# Power_MPU.net
KiCad netlist of a schematic drawn in Altium Designer
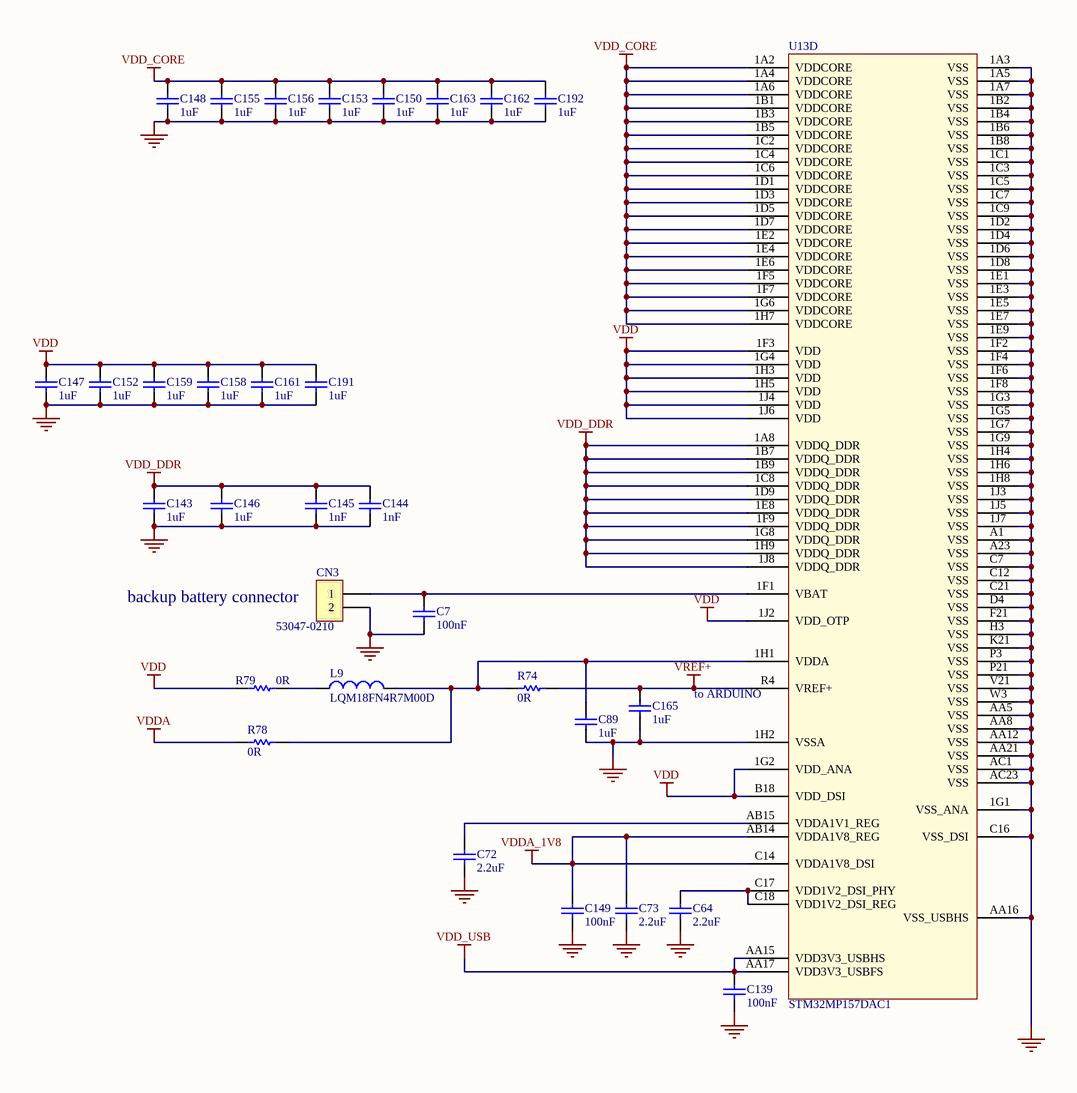
[diagram p0: Power_MPU.SchDoc]

(export (version "E")
  (design (tool "Eeschema 10.0.6"))
  (components
    (comp (ref "C7")
      (value "100nF")
      (footprint "C0402")
      (description "Capacitor,100nF,16V,X7R,10%,0402")
      (fields
        (field (name "INTERNAL_PART_NUMBER") "MCD-00006")
        (field (name "MANUFACTURER_PART_NUMBER") "CC0402KRX7R7BB104")
        (field (name "PROVIDED_BY") "SUBCO")
      )
      (libsource (lib "MCD_PARTS_database") (part "Capacitor"))
    )
    (comp (ref "C64")
      (value "2.2uF")
      (footprint "C0402")
      (description "Capacitor,MLCC,2.2uF,6V3,X5R,10%,0402,T=0.5")
      (fields
        (field (name "INTERNAL_PART_NUMBER") "MCD-01823")
        (field (name "MANUFACTURER_PART_NUMBER") "GRM155R60J225KE95D")
        (field (name "PROVIDED_BY") "SUBCO")
      )
      (libsource (lib "MCD_PARTS_database") (part "Capacitor"))
    )
    (comp (ref "C72")
      (value "2.2uF")
      (footprint "C0402")
      (description "Capacitor,MLCC,2.2uF,6V3,X5R,10%,0402,T=0.5")
      (fields
        (field (name "INTERNAL_PART_NUMBER") "MCD-01823")
        (field (name "MANUFACTURER_PART_NUMBER") "GRM155R60J225KE95D")
        (field (name "PROVIDED_BY") "SUBCO")
      )
      (libsource (lib "MCD_PARTS_database") (part "Capacitor"))
    )
    (comp (ref "C73")
      (value "2.2uF")
      (footprint "C0402")
      (description "Capacitor,MLCC,2.2uF,6V3,X5R,10%,0402,T=0.5")
      (fields
        (field (name "INTERNAL_PART_NUMBER") "MCD-01823")
        (field (name "MANUFACTURER_PART_NUMBER") "GRM155R60J225KE95D")
        (field (name "PROVIDED_BY") "SUBCO")
      )
      (libsource (lib "MCD_PARTS_database") (part "Capacitor"))
    )
    (comp (ref "C89")
      (value "1uF")
      (footprint "C0402")
      (description "Capacitor,1uF,6V3,X5R,10%,0402")
      (fields
        (field (name "INTERNAL_PART_NUMBER") "MCD-00095")
        (field (name "MANUFACTURER_PART_NUMBER") "GRM155R61E105KA12")
        (field (name "PROVIDED_BY") "SUBCO")
      )
      (libsource (lib "MCD_PARTS_database") (part "Capacitor"))
    )
    (comp (ref "C139")
      (value "100nF")
      (footprint "C0402")
      (description "Capacitor,100nF,16V,X7R,10%,0402")
      (fields
        (field (name "INTERNAL_PART_NUMBER") "MCD-00006")
        (field (name "MANUFACTURER_PART_NUMBER") "CC0402KRX7R7BB104")
        (field (name "PROVIDED_BY") "SUBCO")
      )
      (libsource (lib "MCD_PARTS_database") (part "Capacitor"))
    )
    (comp (ref "C143")
      (value "1uF")
      (footprint "C0402")
      (description "Capacitor,1uF,6V3,X5R,10%,0402")
      (fields
        (field (name "INTERNAL_PART_NUMBER") "MCD-00095")
        (field (name "MANUFACTURER_PART_NUMBER") "GRM155R61E105KA12")
        (field (name "PROVIDED_BY") "SUBCO")
      )
      (libsource (lib "MCD_PARTS_database") (part "Capacitor"))
    )
    (comp (ref "C144")
      (value "1nF")
      (footprint "C0402")
      (description "Capacitor,1nF,16V,X7R,10%,0402")
      (fields
        (field (name "INTERNAL_PART_NUMBER") "MCD-00198")
        (field (name "MANUFACTURER_PART_NUMBER") "CC0402KRX7R7BB102")
        (field (name "PROVIDED_BY") "SUBCO")
      )
      (libsource (lib "MCD_PARTS_database") (part "Capacitor"))
    )
    (comp (ref "C145")
      (value "1nF")
      (footprint "C0402")
      (description "Capacitor,1nF,16V,X7R,10%,0402")
      (fields
        (field (name "INTERNAL_PART_NUMBER") "MCD-00198")
        (field (name "MANUFACTURER_PART_NUMBER") "CC0402KRX7R7BB102")
        (field (name "PROVIDED_BY") "SUBCO")
      )
      (libsource (lib "MCD_PARTS_database") (part "Capacitor"))
    )
    (comp (ref "C146")
      (value "1uF")
      (footprint "C0402")
      (description "Capacitor,1uF,6V3,X5R,10%,0402")
      (fields
        (field (name "INTERNAL_PART_NUMBER") "MCD-00095")
        (field (name "MANUFACTURER_PART_NUMBER") "GRM155R61E105KA12")
        (field (name "PROVIDED_BY") "SUBCO")
      )
      (libsource (lib "MCD_PARTS_database") (part "Capacitor"))
    )
    (comp (ref "C147")
      (value "1uF")
      (footprint "C0402")
      (description "Capacitor,1uF,6V3,X5R,10%,0402")
      (fields
        (field (name "INTERNAL_PART_NUMBER") "MCD-00095")
        (field (name "MANUFACTURER_PART_NUMBER") "GRM155R61E105KA12")
        (field (name "PROVIDED_BY") "SUBCO")
      )
      (libsource (lib "MCD_PARTS_database") (part "Capacitor"))
    )
    (comp (ref "C148")
      (value "1uF")
      (footprint "C0402")
      (description "Capacitor,1uF,6V3,X5R,10%,0402")
      (fields
        (field (name "INTERNAL_PART_NUMBER") "MCD-00095")
        (field (name "MANUFACTURER_PART_NUMBER") "GRM155R61E105KA12")
        (field (name "PROVIDED_BY") "SUBCO")
      )
      (libsource (lib "MCD_PARTS_database") (part "Capacitor"))
    )
    (comp (ref "C149")
      (value "100nF")
      (footprint "C0402")
      (description "Capacitor,100nF,16V,X7R,10%,0402")
      (fields
        (field (name "INTERNAL_PART_NUMBER") "MCD-00006")
        (field (name "MANUFACTURER_PART_NUMBER") "CC0402KRX7R7BB104")
        (field (name "PROVIDED_BY") "SUBCO")
      )
      (libsource (lib "MCD_PARTS_database") (part "Capacitor"))
    )
    (comp (ref "C150")
      (value "1uF")
      (footprint "C0402")
      (description "Capacitor,1uF,6V3,X5R,10%,0402")
      (fields
        (field (name "INTERNAL_PART_NUMBER") "MCD-00095")
        (field (name "MANUFACTURER_PART_NUMBER") "GRM155R61E105KA12")
        (field (name "PROVIDED_BY") "SUBCO")
      )
      (libsource (lib "MCD_PARTS_database") (part "Capacitor"))
    )
    (comp (ref "C152")
      (value "1uF")
      (footprint "C0402")
      (description "Capacitor,1uF,6V3,X5R,10%,0402")
      (fields
        (field (name "INTERNAL_PART_NUMBER") "MCD-00095")
        (field (name "MANUFACTURER_PART_NUMBER") "GRM155R61E105KA12")
        (field (name "PROVIDED_BY") "SUBCO")
      )
      (libsource (lib "MCD_PARTS_database") (part "Capacitor"))
    )
    (comp (ref "C153")
      (value "1uF")
      (footprint "C0402")
      (description "Capacitor,1uF,6V3,X5R,10%,0402")
      (fields
        (field (name "INTERNAL_PART_NUMBER") "MCD-00095")
        (field (name "MANUFACTURER_PART_NUMBER") "GRM155R61E105KA12")
        (field (name "PROVIDED_BY") "SUBCO")
      )
      (libsource (lib "MCD_PARTS_database") (part "Capacitor"))
    )
    (comp (ref "C155")
      (value "1uF")
      (footprint "C0402")
      (description "Capacitor,1uF,6V3,X5R,10%,0402")
      (fields
        (field (name "INTERNAL_PART_NUMBER") "MCD-00095")
        (field (name "MANUFACTURER_PART_NUMBER") "GRM155R61E105KA12")
        (field (name "PROVIDED_BY") "SUBCO")
      )
      (libsource (lib "MCD_PARTS_database") (part "Capacitor"))
    )
    (comp (ref "C156")
      (value "1uF")
      (footprint "C0402")
      (description "Capacitor,1uF,6V3,X5R,10%,0402")
      (fields
        (field (name "INTERNAL_PART_NUMBER") "MCD-00095")
        (field (name "MANUFACTURER_PART_NUMBER") "GRM155R61E105KA12")
        (field (name "PROVIDED_BY") "SUBCO")
      )
      (libsource (lib "MCD_PARTS_database") (part "Capacitor"))
    )
    (comp (ref "C158")
      (value "1uF")
      (footprint "C0402")
      (description "Capacitor,1uF,6V3,X5R,10%,0402")
      (fields
        (field (name "INTERNAL_PART_NUMBER") "MCD-00095")
        (field (name "MANUFACTURER_PART_NUMBER") "GRM155R61E105KA12")
        (field (name "PROVIDED_BY") "SUBCO")
      )
      (libsource (lib "MCD_PARTS_database") (part "Capacitor"))
    )
    (comp (ref "C159")
      (value "1uF")
      (footprint "C0402")
      (description "Capacitor,1uF,6V3,X5R,10%,0402")
      (fields
        (field (name "INTERNAL_PART_NUMBER") "MCD-00095")
        (field (name "MANUFACTURER_PART_NUMBER") "GRM155R61E105KA12")
        (field (name "PROVIDED_BY") "SUBCO")
      )
      (libsource (lib "MCD_PARTS_database") (part "Capacitor"))
    )
    (comp (ref "C161")
      (value "1uF")
      (footprint "C0402")
      (description "Capacitor,1uF,6V3,X5R,10%,0402")
      (fields
        (field (name "INTERNAL_PART_NUMBER") "MCD-00095")
        (field (name "MANUFACTURER_PART_NUMBER") "GRM155R61E105KA12")
        (field (name "PROVIDED_BY") "SUBCO")
      )
      (libsource (lib "MCD_PARTS_database") (part "Capacitor"))
    )
    (comp (ref "C162")
      (value "1uF")
      (footprint "C0402")
      (description "Capacitor,1uF,6V3,X5R,10%,0402")
      (fields
        (field (name "INTERNAL_PART_NUMBER") "MCD-00095")
        (field (name "MANUFACTURER_PART_NUMBER") "GRM155R61E105KA12")
        (field (name "PROVIDED_BY") "SUBCO")
      )
      (libsource (lib "MCD_PARTS_database") (part "Capacitor"))
    )
    (comp (ref "C163")
      (value "1uF")
      (footprint "C0402")
      (description "Capacitor,1uF,6V3,X5R,10%,0402")
      (fields
        (field (name "INTERNAL_PART_NUMBER") "MCD-00095")
        (field (name "MANUFACTURER_PART_NUMBER") "GRM155R61E105KA12")
        (field (name "PROVIDED_BY") "SUBCO")
      )
      (libsource (lib "MCD_PARTS_database") (part "Capacitor"))
    )
    (comp (ref "C165")
      (value "1uF")
      (footprint "C0402")
      (description "Capacitor,1uF,6V3,X5R,10%,0402")
      (fields
        (field (name "INTERNAL_PART_NUMBER") "MCD-00095")
        (field (name "MANUFACTURER_PART_NUMBER") "GRM155R61E105KA12")
        (field (name "PROVIDED_BY") "SUBCO")
      )
      (libsource (lib "MCD_PARTS_database") (part "Capacitor"))
    )
    (comp (ref "C191")
      (value "1uF")
      (footprint "C0402")
      (description "Capacitor,1uF,6V3,X5R,10%,0402")
      (fields
        (field (name "INTERNAL_PART_NUMBER") "MCD-00095")
        (field (name "MANUFACTURER_PART_NUMBER") "GRM155R61E105KA12")
        (field (name "PROVIDED_BY") "SUBCO")
      )
      (libsource (lib "MCD_PARTS_database") (part "Capacitor"))
    )
    (comp (ref "C192")
      (value "1uF")
      (footprint "C0402")
      (description "Capacitor,1uF,6V3,X5R,10%,0402")
      (fields
        (field (name "INTERNAL_PART_NUMBER") "MCD-00095")
        (field (name "MANUFACTURER_PART_NUMBER") "GRM155R61E105KA12")
        (field (name "PROVIDED_BY") "SUBCO")
      )
      (libsource (lib "MCD_PARTS_database") (part "Capacitor"))
    )
    (comp (ref "CN3")
      (value "53047-0210")
      (footprint "CON_MOLEX_53047-0210")
      (description "Header 2 circuits, 1.25mm Pitch ,  Vertical, with Friction Lock")
      (fields
        (field (name "INTERNAL_PART_NUMBER") "MCD-00655")
        (field (name "MANUFACTURER") "MOLEX")
        (field (name "PROVIDED_BY") "SUBCO")
      )
      (libsource (lib "MCD_PARTS_database") (part "Header 2x1"))
    )
    (comp (ref "L9")
      (value "LQM18FN4R7M00D")
      (footprint "L0603")
      (description "IND 4.7µH 20% 80mA 600mhom 0603")
      (fields
        (field (name "INTERNAL_PART_NUMBER") "MCD-01134")
        (field (name "MANUFACTURER") "MURATA")
        (field (name "PROVIDED_BY") "SUBCO")
      )
      (libsource (lib "MCD_PARTS_database") (part "LQM18FN4R7M00D"))
    )
    (comp (ref "R74")
      (value "0R")
      (footprint "R0402")
      (description "Resistor,0R,0402,5%,1/16W")
      (fields
        (field (name "INTERNAL_PART_NUMBER") "MCD-00052")
        (field (name "MANUFACTURER_PART_NUMBER") "RC0402JR-070RL")
        (field (name "PROVIDED_BY") "SUBCO")
      )
      (libsource (lib "MCD_PARTS_database") (part "Resistor"))
    )
    (comp (ref "R78")
      (value "0R")
      (footprint "R0402")
      (description "Resistor,0R,0402,5%,1/16W")
      (fields
        (field (name "INTERNAL_PART_NUMBER") "MCD-00052")
        (field (name "MANUFACTURER_PART_NUMBER") "RC0402JR-070RL")
        (field (name "PROVIDED_BY") "SUBCO")
      )
      (libsource (lib "MCD_PARTS_database") (part "Resistor"))
    )
    (comp (ref "R79")
      (value "0R")
      (footprint "R0402")
      (description "Resistor,0R,0402,5%,1/16W")
      (fields
        (field (name "INTERNAL_PART_NUMBER") "MCD-00052")
        (field (name "MANUFACTURER_PART_NUMBER") "RC0402JR-070RL")
        (field (name "PROVIDED_BY") "SUBCO")
      )
      (libsource (lib "MCD_PARTS_database") (part "Resistor"))
    )
    (comp (ref "U13")
      (value "STM32MP157DAC1")
      (footprint "ICC_TFBGA361_12X12_STM32MP157CAC3_P050-065")
      (description "MPU TFBGA12x12 without crypto increased frequency")
      (fields
        (field (name "INTERNAL_PART_NUMBER") "MCD-02020")
        (field (name "MANUFACTURER") "STMICROELECTRONICS")
        (field (name "PROVIDED_BY") "SUBCO with ST control")
      )
      (libsource (lib "MCD_PARTS_database") (part "STM32MP157DAC1"))
    )
  )
  (nets
    (net (code "1") (name "GND") (class "Default")
      (node (ref "C139") (pin "1") (pinfunction "1_1") (pintype "passive"))
      (node (ref "C143") (pin "1") (pinfunction "1_1") (pintype "passive"))
      (node (ref "C144") (pin "1") (pinfunction "1_1") (pintype "passive"))
      (node (ref "C145") (pin "1") (pinfunction "1_1") (pintype "passive"))
      (node (ref "C146") (pin "1") (pinfunction "1_1") (pintype "passive"))
      (node (ref "C147") (pin "1") (pinfunction "1_1") (pintype "passive"))
      (node (ref "C148") (pin "1") (pinfunction "1_1") (pintype "passive"))
      (node (ref "C149") (pin "1") (pinfunction "1_1") (pintype "passive"))
      (node (ref "C150") (pin "1") (pinfunction "1_1") (pintype "passive"))
      (node (ref "C152") (pin "1") (pinfunction "1_1") (pintype "passive"))
      (node (ref "C153") (pin "1") (pinfunction "1_1") (pintype "passive"))
      (node (ref "C155") (pin "1") (pinfunction "1_1") (pintype "passive"))
      (node (ref "C156") (pin "1") (pinfunction "1_1") (pintype "passive"))
      (node (ref "C158") (pin "1") (pinfunction "1_1") (pintype "passive"))
      (node (ref "C159") (pin "1") (pinfunction "1_1") (pintype "passive"))
      (node (ref "C161") (pin "1") (pinfunction "1_1") (pintype "passive"))
      (node (ref "C162") (pin "1") (pinfunction "1_1") (pintype "passive"))
      (node (ref "C163") (pin "1") (pinfunction "1_1") (pintype "passive"))
      (node (ref "C165") (pin "1") (pinfunction "1_1") (pintype "passive"))
      (node (ref "C191") (pin "1") (pinfunction "1_1") (pintype "passive"))
      (node (ref "C192") (pin "1") (pinfunction "1_1") (pintype "passive"))
      (node (ref "C64") (pin "2") (pinfunction "2_2") (pintype "passive"))
      (node (ref "C7") (pin "1") (pinfunction "1_1") (pintype "passive"))
      (node (ref "C72") (pin "2") (pinfunction "2_2") (pintype "passive"))
      (node (ref "C73") (pin "2") (pinfunction "2_2") (pintype "passive"))
      (node (ref "C89") (pin "1") (pinfunction "1_1") (pintype "passive"))
      (node (ref "CN3") (pin "2") (pinfunction "2_2") (pintype "passive"))
      (node (ref "U13") (pin "1A3") (pinfunction "VSS_1A3") (pintype "passive"))
      (node (ref "U13") (pin "1A5") (pinfunction "VSS_1A5") (pintype "passive"))
      (node (ref "U13") (pin "1A7") (pinfunction "VSS_1A7") (pintype "passive"))
      (node (ref "U13") (pin "1B2") (pinfunction "VSS_1B2") (pintype "passive"))
      (node (ref "U13") (pin "1B4") (pinfunction "VSS_1B4") (pintype "passive"))
      (node (ref "U13") (pin "1B6") (pinfunction "VSS_1B6") (pintype "passive"))
      (node (ref "U13") (pin "1B8") (pinfunction "VSS_1B8") (pintype "passive"))
      (node (ref "U13") (pin "1C1") (pinfunction "VSS_1C1") (pintype "passive"))
      (node (ref "U13") (pin "1C3") (pinfunction "VSS_1C3") (pintype "passive"))
      (node (ref "U13") (pin "1C5") (pinfunction "VSS_1C5") (pintype "passive"))
      (node (ref "U13") (pin "1C7") (pinfunction "VSS_1C7") (pintype "passive"))
      (node (ref "U13") (pin "1C9") (pinfunction "VSS_1C9") (pintype "passive"))
      (node (ref "U13") (pin "1D2") (pinfunction "VSS_1D2") (pintype "passive"))
      (node (ref "U13") (pin "1D4") (pinfunction "VSS_1D4") (pintype "passive"))
      (node (ref "U13") (pin "1D6") (pinfunction "VSS_1D6") (pintype "passive"))
      (node (ref "U13") (pin "1D8") (pinfunction "VSS_1D8") (pintype "passive"))
      (node (ref "U13") (pin "1E1") (pinfunction "VSS_1E1") (pintype "passive"))
      (node (ref "U13") (pin "1E3") (pinfunction "VSS_1E3") (pintype "passive"))
      (node (ref "U13") (pin "1E5") (pinfunction "VSS_1E5") (pintype "passive"))
      (node (ref "U13") (pin "1E7") (pinfunction "VSS_1E7") (pintype "passive"))
      (node (ref "U13") (pin "1E9") (pinfunction "VSS_1E9") (pintype "passive"))
      (node (ref "U13") (pin "1F2") (pinfunction "VSS_1F2") (pintype "passive"))
      (node (ref "U13") (pin "1F4") (pinfunction "VSS_1F4") (pintype "passive"))
      (node (ref "U13") (pin "1F6") (pinfunction "VSS_1F6") (pintype "passive"))
      (node (ref "U13") (pin "1F8") (pinfunction "VSS_1F8") (pintype "passive"))
      (node (ref "U13") (pin "1G1") (pinfunction "VSS_ANA_1G1") (pintype "passive"))
      (node (ref "U13") (pin "1G3") (pinfunction "VSS_1G3") (pintype "passive"))
      (node (ref "U13") (pin "1G5") (pinfunction "VSS_1G5") (pintype "passive"))
      (node (ref "U13") (pin "1G7") (pinfunction "VSS_1G7") (pintype "passive"))
      (node (ref "U13") (pin "1G9") (pinfunction "VSS_1G9") (pintype "passive"))
      (node (ref "U13") (pin "1H2") (pinfunction "VSSA_1H2") (pintype "passive"))
      (node (ref "U13") (pin "1H4") (pinfunction "VSS_1H4") (pintype "passive"))
      (node (ref "U13") (pin "1H6") (pinfunction "VSS_1H6") (pintype "passive"))
      (node (ref "U13") (pin "1H8") (pinfunction "VSS_1H8") (pintype "passive"))
      (node (ref "U13") (pin "1J3") (pinfunction "VSS_1J3") (pintype "passive"))
      (node (ref "U13") (pin "1J5") (pinfunction "VSS_1J5") (pintype "passive"))
      (node (ref "U13") (pin "1J7") (pinfunction "VSS_1J7") (pintype "passive"))
      (node (ref "U13") (pin "A1") (pinfunction "VSS_A1") (pintype "passive"))
      (node (ref "U13") (pin "A23") (pinfunction "VSS_A23") (pintype "passive"))
      (node (ref "U13") (pin "AA12") (pinfunction "VSS_AA12") (pintype "passive"))
      (node (ref "U13") (pin "AA16") (pinfunction "VSS_USBHS_AA16") (pintype "passive"))
      (node (ref "U13") (pin "AA21") (pinfunction "VSS_AA21") (pintype "passive"))
      (node (ref "U13") (pin "AA5") (pinfunction "VSS_AA5") (pintype "passive"))
      (node (ref "U13") (pin "AA8") (pinfunction "VSS_AA8") (pintype "passive"))
      (node (ref "U13") (pin "AC1") (pinfunction "VSS_AC1") (pintype "passive"))
      (node (ref "U13") (pin "AC23") (pinfunction "VSS_AC23") (pintype "passive"))
      (node (ref "U13") (pin "C12") (pinfunction "VSS_C12") (pintype "passive"))
      (node (ref "U13") (pin "C16") (pinfunction "VSS_DSI_C16") (pintype "passive"))
      (node (ref "U13") (pin "C21") (pinfunction "VSS_C21") (pintype "passive"))
      (node (ref "U13") (pin "C7") (pinfunction "VSS_C7") (pintype "passive"))
      (node (ref "U13") (pin "D4") (pinfunction "VSS_D4") (pintype "passive"))
      (node (ref "U13") (pin "F21") (pinfunction "VSS_F21") (pintype "passive"))
      (node (ref "U13") (pin "H3") (pinfunction "VSS_H3") (pintype "passive"))
      (node (ref "U13") (pin "K21") (pinfunction "VSS_K21") (pintype "passive"))
      (node (ref "U13") (pin "P21") (pinfunction "VSS_P21") (pintype "passive"))
      (node (ref "U13") (pin "P3") (pinfunction "VSS_P3") (pintype "passive"))
      (node (ref "U13") (pin "V21") (pinfunction "VSS_V21") (pintype "passive"))
      (node (ref "U13") (pin "W3") (pinfunction "VSS_W3") (pintype "passive"))
    )
    (net (code "2") (name "Net-(L9-Pad1)") (class "Default")
      (node (ref "L9") (pin "1") (pinfunction "1_1") (pintype "passive"))
      (node (ref "R79") (pin "2") (pinfunction "2_2") (pintype "passive"))
    )
    (net (code "3") (name "Net-(U13D-VBAT)") (class "Default")
      (node (ref "C7") (pin "2") (pinfunction "2_2") (pintype "passive"))
      (node (ref "CN3") (pin "1") (pinfunction "1_1") (pintype "passive"))
      (node (ref "U13") (pin "1F1") (pinfunction "VBAT_1F1") (pintype "passive"))
    )
    (net (code "4") (name "Net-(U13D-VDD1V2_DSI_PHY)") (class "Default")
      (node (ref "C64") (pin "1") (pinfunction "1_1") (pintype "passive"))
      (node (ref "U13") (pin "C17") (pinfunction "VDD1V2_DSI_PHY_C17") (pintype "passive"))
      (node (ref "U13") (pin "C18") (pinfunction "VDD1V2_DSI_REG_C18") (pintype "passive"))
    )
    (net (code "5") (name "Net-(U13D-VDDA)") (class "Default")
      (node (ref "C89") (pin "2") (pinfunction "2_2") (pintype "passive"))
      (node (ref "L9") (pin "2") (pinfunction "2_2") (pintype "passive"))
      (node (ref "R74") (pin "1") (pinfunction "1_1") (pintype "passive"))
      (node (ref "R78") (pin "2") (pinfunction "2_2") (pintype "passive"))
      (node (ref "U13") (pin "1H1") (pinfunction "VDDA_1H1") (pintype "passive"))
    )
    (net (code "6") (name "Net-(U13D-VDDA1V1_REG)") (class "Default")
      (node (ref "C72") (pin "1") (pinfunction "1_1") (pintype "passive"))
      (node (ref "U13") (pin "AB15") (pinfunction "VDDA1V1_REG_AB15") (pintype "passive"))
    )
    (net (code "7") (name "VDD") (class "Default")
      (node (ref "C147") (pin "2") (pinfunction "2_2") (pintype "passive"))
      (node (ref "C152") (pin "2") (pinfunction "2_2") (pintype "passive"))
      (node (ref "C158") (pin "2") (pinfunction "2_2") (pintype "passive"))
      (node (ref "C159") (pin "2") (pinfunction "2_2") (pintype "passive"))
      (node (ref "C161") (pin "2") (pinfunction "2_2") (pintype "passive"))
      (node (ref "C191") (pin "2") (pinfunction "2_2") (pintype "passive"))
      (node (ref "R79") (pin "1") (pinfunction "1_1") (pintype "passive"))
      (node (ref "U13") (pin "1F3") (pinfunction "VDD_1F3") (pintype "passive"))
      (node (ref "U13") (pin "1G2") (pinfunction "VDD_ANA_1G2") (pintype "passive"))
      (node (ref "U13") (pin "1G4") (pinfunction "VDD_1G4") (pintype "passive"))
      (node (ref "U13") (pin "1H3") (pinfunction "VDD_1H3") (pintype "passive"))
      (node (ref "U13") (pin "1H5") (pinfunction "VDD_1H5") (pintype "passive"))
      (node (ref "U13") (pin "1J2") (pinfunction "VDD_OTP_1J2") (pintype "passive"))
      (node (ref "U13") (pin "1J4") (pinfunction "VDD_1J4") (pintype "passive"))
      (node (ref "U13") (pin "1J6") (pinfunction "VDD_1J6") (pintype "passive"))
      (node (ref "U13") (pin "B18") (pinfunction "VDD_DSI_B18") (pintype "passive"))
    )
    (net (code "8") (name "VDDA") (class "Default")
      (node (ref "R78") (pin "1") (pinfunction "1_1") (pintype "passive"))
    )
    (net (code "9") (name "VDDA_1V8") (class "Default")
      (node (ref "C149") (pin "2") (pinfunction "2_2") (pintype "passive"))
      (node (ref "C73") (pin "1") (pinfunction "1_1") (pintype "passive"))
      (node (ref "U13") (pin "AB14") (pinfunction "VDDA1V8_REG_AB14") (pintype "passive"))
      (node (ref "U13") (pin "C14") (pinfunction "VDDA1V8_DSI_C14") (pintype "passive"))
    )
    (net (code "10") (name "VDD_CORE") (class "Default")
      (node (ref "C148") (pin "2") (pinfunction "2_2") (pintype "passive"))
      (node (ref "C150") (pin "2") (pinfunction "2_2") (pintype "passive"))
      (node (ref "C153") (pin "2") (pinfunction "2_2") (pintype "passive"))
      (node (ref "C155") (pin "2") (pinfunction "2_2") (pintype "passive"))
      (node (ref "C156") (pin "2") (pinfunction "2_2") (pintype "passive"))
      (node (ref "C162") (pin "2") (pinfunction "2_2") (pintype "passive"))
      (node (ref "C163") (pin "2") (pinfunction "2_2") (pintype "passive"))
      (node (ref "C192") (pin "2") (pinfunction "2_2") (pintype "passive"))
      (node (ref "U13") (pin "1A2") (pinfunction "VDDCORE_1A2") (pintype "passive"))
      (node (ref "U13") (pin "1A4") (pinfunction "VDDCORE_1A4") (pintype "passive"))
      (node (ref "U13") (pin "1A6") (pinfunction "VDDCORE_1A6") (pintype "passive"))
      (node (ref "U13") (pin "1B1") (pinfunction "VDDCORE_1B1") (pintype "passive"))
      (node (ref "U13") (pin "1B3") (pinfunction "VDDCORE_1B3") (pintype "passive"))
      (node (ref "U13") (pin "1B5") (pinfunction "VDDCORE_1B5") (pintype "passive"))
      (node (ref "U13") (pin "1C2") (pinfunction "VDDCORE_1C2") (pintype "passive"))
      (node (ref "U13") (pin "1C4") (pinfunction "VDDCORE_1C4") (pintype "passive"))
      (node (ref "U13") (pin "1C6") (pinfunction "VDDCORE_1C6") (pintype "passive"))
      (node (ref "U13") (pin "1D1") (pinfunction "VDDCORE_1D1") (pintype "passive"))
      (node (ref "U13") (pin "1D3") (pinfunction "VDDCORE_1D3") (pintype "passive"))
      (node (ref "U13") (pin "1D5") (pinfunction "VDDCORE_1D5") (pintype "passive"))
      (node (ref "U13") (pin "1D7") (pinfunction "VDDCORE_1D7") (pintype "passive"))
      (node (ref "U13") (pin "1E2") (pinfunction "VDDCORE_1E2") (pintype "passive"))
      (node (ref "U13") (pin "1E4") (pinfunction "VDDCORE_1E4") (pintype "passive"))
      (node (ref "U13") (pin "1E6") (pinfunction "VDDCORE_1E6") (pintype "passive"))
      (node (ref "U13") (pin "1F5") (pinfunction "VDDCORE_1F5") (pintype "passive"))
      (node (ref "U13") (pin "1F7") (pinfunction "VDDCORE_1F7") (pintype "passive"))
      (node (ref "U13") (pin "1G6") (pinfunction "VDDCORE_1G6") (pintype "passive"))
      (node (ref "U13") (pin "1H7") (pinfunction "VDDCORE_1H7") (pintype "passive"))
    )
    (net (code "11") (name "VDD_DDR") (class "Default")
      (node (ref "C143") (pin "2") (pinfunction "2_2") (pintype "passive"))
      (node (ref "C144") (pin "2") (pinfunction "2_2") (pintype "passive"))
      (node (ref "C145") (pin "2") (pinfunction "2_2") (pintype "passive"))
      (node (ref "C146") (pin "2") (pinfunction "2_2") (pintype "passive"))
      (node (ref "U13") (pin "1A8") (pinfunction "VDDQ_DDR_1A8") (pintype "passive"))
      (node (ref "U13") (pin "1B7") (pinfunction "VDDQ_DDR_1B7") (pintype "passive"))
      (node (ref "U13") (pin "1B9") (pinfunction "VDDQ_DDR_1B9") (pintype "passive"))
      (node (ref "U13") (pin "1C8") (pinfunction "VDDQ_DDR_1C8") (pintype "passive"))
      (node (ref "U13") (pin "1D9") (pinfunction "VDDQ_DDR_1D9") (pintype "passive"))
      (node (ref "U13") (pin "1E8") (pinfunction "VDDQ_DDR_1E8") (pintype "passive"))
      (node (ref "U13") (pin "1F9") (pinfunction "VDDQ_DDR_1F9") (pintype "passive"))
      (node (ref "U13") (pin "1G8") (pinfunction "VDDQ_DDR_1G8") (pintype "passive"))
      (node (ref "U13") (pin "1H9") (pinfunction "VDDQ_DDR_1H9") (pintype "passive"))
      (node (ref "U13") (pin "1J8") (pinfunction "VDDQ_DDR_1J8") (pintype "passive"))
    )
    (net (code "12") (name "VDD_USB") (class "Default")
      (node (ref "C139") (pin "2") (pinfunction "2_2") (pintype "passive"))
      (node (ref "U13") (pin "AA15") (pinfunction "VDD3V3_USBHS_AA15") (pintype "passive"))
      (node (ref "U13") (pin "AA17") (pinfunction "VDD3V3_USBFS_AA17") (pintype "passive"))
    )
    (net (code "13") (name "VREF+") (class "Default")
      (node (ref "C165") (pin "2") (pinfunction "2_2") (pintype "passive"))
      (node (ref "R74") (pin "2") (pinfunction "2_2") (pintype "passive"))
      (node (ref "U13") (pin "R4") (pinfunction "VREF+_R4") (pintype "passive"))
    )
  )
)
